# Sheet2.net
KiCad netlist of a schematic drawn in Altium Designer
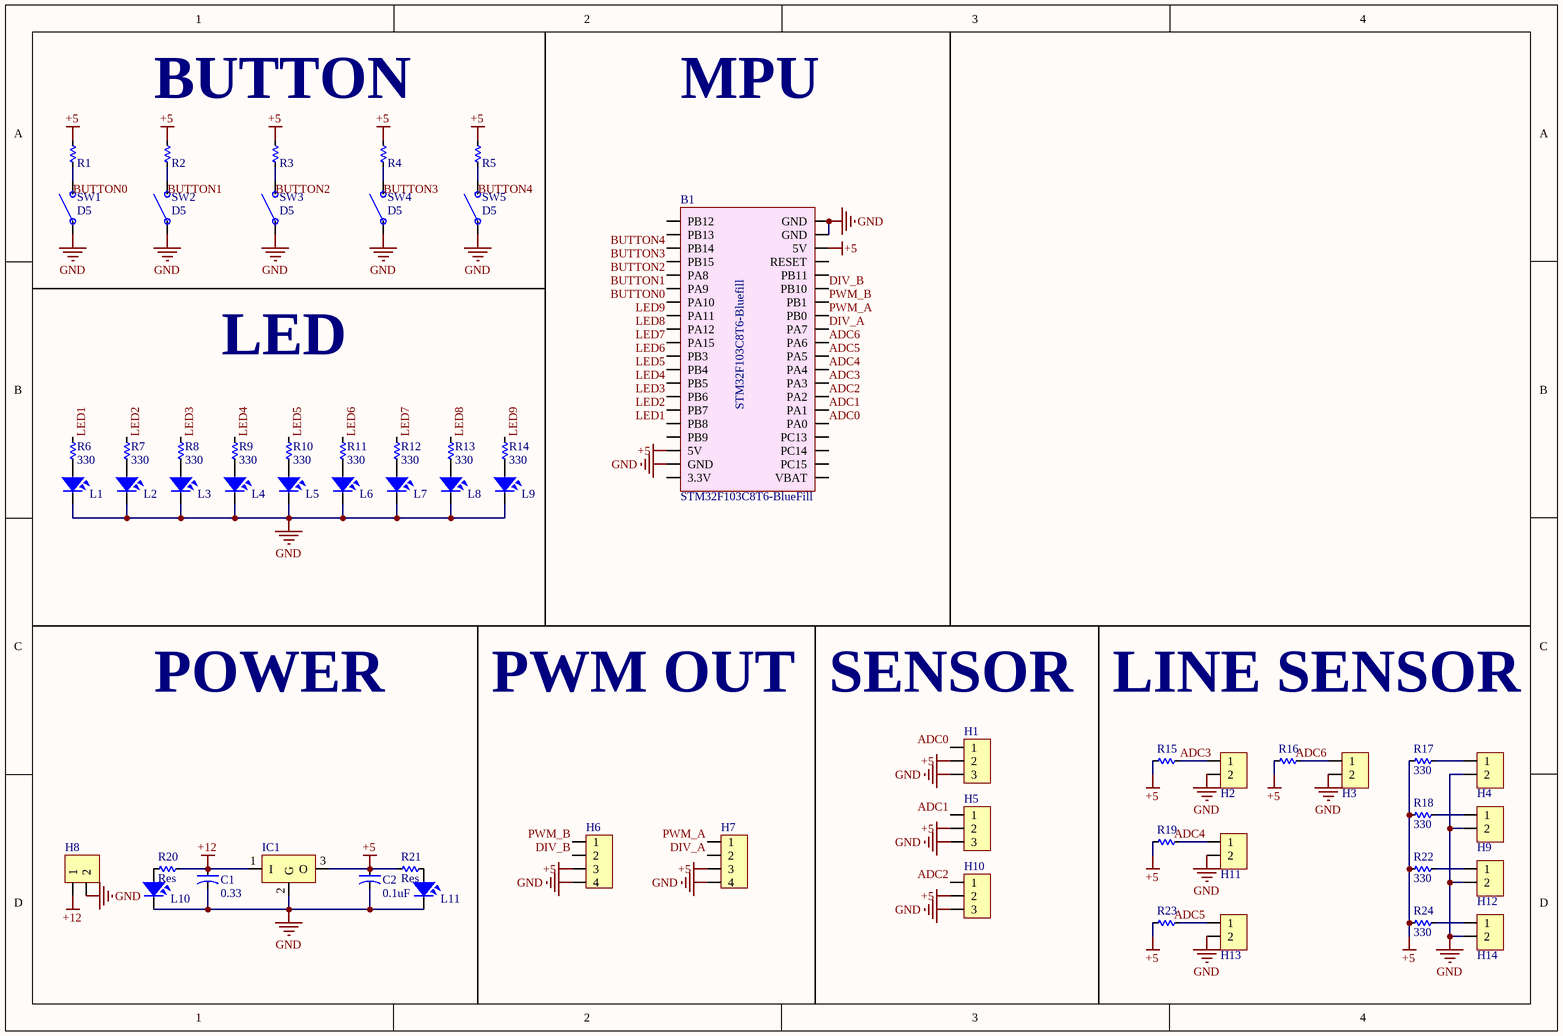
[diagram p0: Sheet2.SchDoc]

(export (version "E")
  (design (tool "Eeschema 10.0.6"))
  (components
    (comp (ref "B1")
      (value "STM32F103C8T6-BlueFill")
      (footprint "STM32F1-Bluefill")
      (libsource (lib "Schlib1") (part "STM32F103C8T6-BlueFill"))
    )
    (comp (ref "C1")
      (value "0.33")
      (footprint "CA-ALU-2.54")
      (description "Capacitor (Semiconductor SIM Model)")
      (fields (field (name "PUBLISHER") "Altium Limited"))
      (libsource (lib "LIBRARY") (part "CN-ALU-DIP"))
    )
    (comp (ref "C2")
      (value "0.1uF")
      (footprint "CA-ALU-2.54")
      (description "Capacitor (Semiconductor SIM Model)")
      (fields (field (name "PUBLISHER") "Altium Limited"))
      (libsource (lib "LIBRARY") (part "CN-ALU-DIP"))
    )
    (comp (ref "H1")
      (value "Header3")
      (footprint "Header3")
      (description "Header IDC, 3 x 1 Pin Vertical 2.54mm Pitch (Non-Boxed, Male)")
      (fields
        (field (name "MANUFACTURER") "Würth Elektronik eiSos GmbH")
        (field (name "PARTNO") "613002143121")
        (field (name "CREATED BY") "Karrer Zheng")
      )
      (libsource (lib "LIBRARY") (part "Header3"))
    )
    (comp (ref "H2")
      (value "Header2")
      (footprint "HDR2")
      (description "Header IDC, 2 x 1 Pin Vertical 2.54mm Pitch (Non-Boxed, Male)")
      (fields
        (field (name "MANUFACTURER") "Würth Elektronik eiSos GmbH")
        (field (name "PARTNO") "613002143121")
        (field (name "CREATED BY") "Karrer Zheng")
      )
      (libsource (lib "LIBRARY") (part "Header2"))
    )
    (comp (ref "H3")
      (value "Header2")
      (footprint "HDR2")
      (description "Header IDC, 2 x 1 Pin Vertical 2.54mm Pitch (Non-Boxed, Male)")
      (fields
        (field (name "MANUFACTURER") "Würth Elektronik eiSos GmbH")
        (field (name "PARTNO") "613002143121")
        (field (name "CREATED BY") "Karrer Zheng")
      )
      (libsource (lib "LIBRARY") (part "Header2"))
    )
    (comp (ref "H4")
      (value "Header2")
      (footprint "HDR2")
      (description "Header IDC, 2 x 1 Pin Vertical 2.54mm Pitch (Non-Boxed, Male)")
      (fields
        (field (name "MANUFACTURER") "Würth Elektronik eiSos GmbH")
        (field (name "PARTNO") "613002143121")
        (field (name "CREATED BY") "Karrer Zheng")
      )
      (libsource (lib "LIBRARY") (part "Header2"))
    )
    (comp (ref "H5")
      (value "Header3")
      (footprint "Header3")
      (description "Header IDC, 3 x 1 Pin Vertical 2.54mm Pitch (Non-Boxed, Male)")
      (fields
        (field (name "MANUFACTURER") "Würth Elektronik eiSos GmbH")
        (field (name "PARTNO") "613002143121")
        (field (name "CREATED BY") "Karrer Zheng")
      )
      (libsource (lib "LIBRARY") (part "Header3"))
    )
    (comp (ref "H6")
      (value "Header4")
      (footprint "Header4")
      (description "Header IDC, 4 x 1 Pin Vertical 2.54mm Pitch (Non-Boxed, Male)")
      (fields
        (field (name "MANUFACTURER") "Würth Elektronik eiSos GmbH")
        (field (name "PARTNO") "613002143121")
        (field (name "CREATED BY") "Karrer Zheng")
      )
      (libsource (lib "LIBRARY") (part "Header4"))
    )
    (comp (ref "H7")
      (value "Header4")
      (footprint "Header4")
      (description "Header IDC, 4 x 1 Pin Vertical 2.54mm Pitch (Non-Boxed, Male)")
      (fields
        (field (name "MANUFACTURER") "Würth Elektronik eiSos GmbH")
        (field (name "PARTNO") "613002143121")
        (field (name "CREATED BY") "Karrer Zheng")
      )
      (libsource (lib "LIBRARY") (part "Header4"))
    )
    (comp (ref "H8")
      (value "Header2")
      (footprint "HDR2")
      (description "Header IDC, 2 x 1 Pin Vertical 2.54mm Pitch (Non-Boxed, Male)")
      (fields
        (field (name "MANUFACTURER") "Würth Elektronik eiSos GmbH")
        (field (name "PARTNO") "613002143121")
        (field (name "CREATED BY") "Karrer Zheng")
      )
      (libsource (lib "") (part "Header2_1"))
    )
    (comp (ref "H9")
      (value "Header2")
      (footprint "HDR2")
      (description "Header IDC, 2 x 1 Pin Vertical 2.54mm Pitch (Non-Boxed, Male)")
      (fields
        (field (name "MANUFACTURER") "Würth Elektronik eiSos GmbH")
        (field (name "PARTNO") "613002143121")
        (field (name "CREATED BY") "Karrer Zheng")
      )
      (libsource (lib "LIBRARY") (part "Header2"))
    )
    (comp (ref "H10")
      (value "Header3")
      (footprint "Header3")
      (description "Header IDC, 3 x 1 Pin Vertical 2.54mm Pitch (Non-Boxed, Male)")
      (fields
        (field (name "MANUFACTURER") "Würth Elektronik eiSos GmbH")
        (field (name "PARTNO") "613002143121")
        (field (name "CREATED BY") "Karrer Zheng")
      )
      (libsource (lib "LIBRARY") (part "Header3"))
    )
    (comp (ref "H11")
      (value "Header2")
      (footprint "HDR2")
      (description "Header IDC, 2 x 1 Pin Vertical 2.54mm Pitch (Non-Boxed, Male)")
      (fields
        (field (name "MANUFACTURER") "Würth Elektronik eiSos GmbH")
        (field (name "PARTNO") "613002143121")
        (field (name "CREATED BY") "Karrer Zheng")
      )
      (libsource (lib "LIBRARY") (part "Header2"))
    )
    (comp (ref "H12")
      (value "Header2")
      (footprint "HDR2")
      (description "Header IDC, 2 x 1 Pin Vertical 2.54mm Pitch (Non-Boxed, Male)")
      (fields
        (field (name "MANUFACTURER") "Würth Elektronik eiSos GmbH")
        (field (name "PARTNO") "613002143121")
        (field (name "CREATED BY") "Karrer Zheng")
      )
      (libsource (lib "LIBRARY") (part "Header2"))
    )
    (comp (ref "H13")
      (value "Header2")
      (footprint "HDR2")
      (description "Header IDC, 2 x 1 Pin Vertical 2.54mm Pitch (Non-Boxed, Male)")
      (fields
        (field (name "MANUFACTURER") "Würth Elektronik eiSos GmbH")
        (field (name "PARTNO") "613002143121")
        (field (name "CREATED BY") "Karrer Zheng")
      )
      (libsource (lib "LIBRARY") (part "Header2"))
    )
    (comp (ref "H14")
      (value "Header2")
      (footprint "HDR2")
      (description "Header IDC, 2 x 1 Pin Vertical 2.54mm Pitch (Non-Boxed, Male)")
      (fields
        (field (name "MANUFACTURER") "Würth Elektronik eiSos GmbH")
        (field (name "PARTNO") "613002143121")
        (field (name "CREATED BY") "Karrer Zheng")
      )
      (libsource (lib "LIBRARY") (part "Header2"))
    )
    (comp (ref "IC1")
      (value "LM78xx")
      (footprint "TO220-123")
      (description "Positive Voltage Regulator")
      (fields (field (name "PUBLISHER") "Altium Limited"))
      (libsource (lib "LIBRARY") (part "LM78xx"))
    )
    (comp (ref "L1")
      (value "LED")
      (footprint "LED-3MM-YELLOW")
      (description "LED Single colour Green and Red")
      (libsource (lib "LIBRARY") (part "LED"))
    )
    (comp (ref "L2")
      (value "LED")
      (footprint "LED-3MM-YELLOW")
      (description "LED Single colour Green and Red")
      (libsource (lib "LIBRARY") (part "LED"))
    )
    (comp (ref "L3")
      (value "LED")
      (footprint "LED-3MM-YELLOW")
      (description "LED Single colour Green and Red")
      (libsource (lib "LIBRARY") (part "LED"))
    )
    (comp (ref "L4")
      (value "LED")
      (footprint "LED-3MM-YELLOW")
      (description "LED Single colour Green and Red")
      (libsource (lib "LIBRARY") (part "LED"))
    )
    (comp (ref "L5")
      (value "LED")
      (footprint "LED-3MM-YELLOW")
      (description "LED Single colour Green and Red")
      (libsource (lib "LIBRARY") (part "LED"))
    )
    (comp (ref "L6")
      (value "LED")
      (footprint "LED-3MM-YELLOW")
      (description "LED Single colour Green and Red")
      (libsource (lib "LIBRARY") (part "LED"))
    )
    (comp (ref "L7")
      (value "LED")
      (footprint "LED-3MM-YELLOW")
      (description "LED Single colour Green and Red")
      (libsource (lib "LIBRARY") (part "LED"))
    )
    (comp (ref "L8")
      (value "LED")
      (footprint "LED-3MM-YELLOW")
      (description "LED Single colour Green and Red")
      (libsource (lib "LIBRARY") (part "LED"))
    )
    (comp (ref "L9")
      (value "LED")
      (footprint "LED-3MM-YELLOW")
      (description "LED Single colour Green and Red")
      (libsource (lib "LIBRARY") (part "LED"))
    )
    (comp (ref "L10")
      (value "LED")
      (footprint "LED-3MM-YELLOW")
      (description "LED Single colour Green and Red")
      (libsource (lib "LIBRARY") (part "LED"))
    )
    (comp (ref "L11")
      (value "LED")
      (footprint "LED-3MM-YELLOW")
      (description "LED Single colour Green and Red")
      (libsource (lib "LIBRARY") (part "LED"))
    )
    (comp (ref "R1")
      (value "10K")
      (footprint "RES-1/4WD")
      (description "Res")
      (fields
        (field (name "MANUFACTURER") "Generic Components")
        (field (name "PUBLISHER") "Altium Hobart Technology Centre")
      )
      (libsource (lib "LIBRARY") (part "Res"))
    )
    (comp (ref "R2")
      (value "10K")
      (footprint "RES-1/4WD")
      (description "Res")
      (fields
        (field (name "MANUFACTURER") "Generic Components")
        (field (name "PUBLISHER") "Altium Hobart Technology Centre")
      )
      (libsource (lib "LIBRARY") (part "Res"))
    )
    (comp (ref "R3")
      (value "10K")
      (footprint "RES-1/4WD")
      (description "Res")
      (fields
        (field (name "MANUFACTURER") "Generic Components")
        (field (name "PUBLISHER") "Altium Hobart Technology Centre")
      )
      (libsource (lib "LIBRARY") (part "Res"))
    )
    (comp (ref "R4")
      (value "10K")
      (footprint "RES-1/4WD")
      (description "Res")
      (fields
        (field (name "MANUFACTURER") "Generic Components")
        (field (name "PUBLISHER") "Altium Hobart Technology Centre")
      )
      (libsource (lib "LIBRARY") (part "Res"))
    )
    (comp (ref "R5")
      (value "10K")
      (footprint "RES-1/4WD")
      (description "Res")
      (fields
        (field (name "MANUFACTURER") "Generic Components")
        (field (name "PUBLISHER") "Altium Hobart Technology Centre")
      )
      (libsource (lib "LIBRARY") (part "Res"))
    )
    (comp (ref "R6")
      (value "330")
      (footprint "RES-1/4W-SMALL")
      (description "Res")
      (fields
        (field (name "MANUFACTURER") "Generic Components")
        (field (name "PUBLISHER") "Altium Hobart Technology Centre")
      )
      (libsource (lib "LIBRARY") (part "Res"))
    )
    (comp (ref "R7")
      (value "330")
      (footprint "RES-1/4W-SMALL")
      (description "Res")
      (fields
        (field (name "MANUFACTURER") "Generic Components")
        (field (name "PUBLISHER") "Altium Hobart Technology Centre")
      )
      (libsource (lib "LIBRARY") (part "Res"))
    )
    (comp (ref "R8")
      (value "330")
      (footprint "RES-1/4W-SMALL")
      (description "Res")
      (fields
        (field (name "MANUFACTURER") "Generic Components")
        (field (name "PUBLISHER") "Altium Hobart Technology Centre")
      )
      (libsource (lib "LIBRARY") (part "Res"))
    )
    (comp (ref "R9")
      (value "330")
      (footprint "RES-1/4W-SMALL")
      (description "Res")
      (fields
        (field (name "MANUFACTURER") "Generic Components")
        (field (name "PUBLISHER") "Altium Hobart Technology Centre")
      )
      (libsource (lib "LIBRARY") (part "Res"))
    )
    (comp (ref "R10")
      (value "330")
      (footprint "RES-1/4W-SMALL")
      (description "Res")
      (fields
        (field (name "MANUFACTURER") "Generic Components")
        (field (name "PUBLISHER") "Altium Hobart Technology Centre")
      )
      (libsource (lib "LIBRARY") (part "Res"))
    )
    (comp (ref "R11")
      (value "330")
      (footprint "RES-1/4W-SMALL")
      (description "Res")
      (fields
        (field (name "MANUFACTURER") "Generic Components")
        (field (name "PUBLISHER") "Altium Hobart Technology Centre")
      )
      (libsource (lib "LIBRARY") (part "Res"))
    )
    (comp (ref "R12")
      (value "330")
      (footprint "RES-1/4W-SMALL")
      (description "Res")
      (fields
        (field (name "MANUFACTURER") "Generic Components")
        (field (name "PUBLISHER") "Altium Hobart Technology Centre")
      )
      (libsource (lib "LIBRARY") (part "Res"))
    )
    (comp (ref "R13")
      (value "330")
      (footprint "RES-1/4W-SMALL")
      (description "Res")
      (fields
        (field (name "MANUFACTURER") "Generic Components")
        (field (name "PUBLISHER") "Altium Hobart Technology Centre")
      )
      (libsource (lib "LIBRARY") (part "Res"))
    )
    (comp (ref "R14")
      (value "330")
      (footprint "RES-1/4W-SMALL")
      (description "Res")
      (fields
        (field (name "MANUFACTURER") "Generic Components")
        (field (name "PUBLISHER") "Altium Hobart Technology Centre")
      )
      (libsource (lib "LIBRARY") (part "Res"))
    )
    (comp (ref "R15")
      (value "10K")
      (footprint "RES-1/4W-SMALL")
      (description "Res")
      (fields
        (field (name "MANUFACTURER") "Generic Components")
        (field (name "PUBLISHER") "Altium Hobart Technology Centre")
      )
      (libsource (lib "LIBRARY") (part "Res"))
    )
    (comp (ref "R16")
      (value "10K")
      (footprint "RES-1/4W-SMALL")
      (description "Res")
      (fields
        (field (name "MANUFACTURER") "Generic Components")
        (field (name "PUBLISHER") "Altium Hobart Technology Centre")
      )
      (libsource (lib "LIBRARY") (part "Res"))
    )
    (comp (ref "R17")
      (value "330")
      (footprint "RES-1/4W-SMALL")
      (description "Res")
      (fields
        (field (name "MANUFACTURER") "Generic Components")
        (field (name "PUBLISHER") "Altium Hobart Technology Centre")
      )
      (libsource (lib "LIBRARY") (part "Res"))
    )
    (comp (ref "R18")
      (value "330")
      (footprint "RES-1/4W-SMALL")
      (description "Res")
      (fields
        (field (name "MANUFACTURER") "Generic Components")
        (field (name "PUBLISHER") "Altium Hobart Technology Centre")
      )
      (libsource (lib "LIBRARY") (part "Res"))
    )
    (comp (ref "R19")
      (value "10K")
      (footprint "RES-1/4W-SMALL")
      (description "Res")
      (fields
        (field (name "MANUFACTURER") "Generic Components")
        (field (name "PUBLISHER") "Altium Hobart Technology Centre")
      )
      (libsource (lib "LIBRARY") (part "Res"))
    )
    (comp (ref "R20")
      (value "Res")
      (footprint "RES-1/4W-SMALL")
      (fields
        (field (name "MANUFACTURER") "Generic Components")
        (field (name "PUBLISHER") "Altium Hobart Technology Centre")
      )
      (libsource (lib "LIBRARY") (part "Res"))
    )
    (comp (ref "R21")
      (value "Res")
      (footprint "RES-1/4W-SMALL")
      (fields
        (field (name "MANUFACTURER") "Generic Components")
        (field (name "PUBLISHER") "Altium Hobart Technology Centre")
      )
      (libsource (lib "LIBRARY") (part "Res"))
    )
    (comp (ref "R22")
      (value "330")
      (footprint "RES-1/4W-SMALL")
      (description "Res")
      (fields
        (field (name "MANUFACTURER") "Generic Components")
        (field (name "PUBLISHER") "Altium Hobart Technology Centre")
      )
      (libsource (lib "LIBRARY") (part "Res"))
    )
    (comp (ref "R23")
      (value "10K")
      (footprint "RES-1/4W-SMALL")
      (description "Res")
      (fields
        (field (name "MANUFACTURER") "Generic Components")
        (field (name "PUBLISHER") "Altium Hobart Technology Centre")
      )
      (libsource (lib "LIBRARY") (part "Res"))
    )
    (comp (ref "R24")
      (value "330")
      (footprint "RES-1/4W-SMALL")
      (description "Res")
      (fields
        (field (name "MANUFACTURER") "Generic Components")
        (field (name "PUBLISHER") "Altium Hobart Technology Centre")
      )
      (libsource (lib "LIBRARY") (part "Res"))
    )
    (comp (ref "SW1") (value "D5") (footprint "D5") (libsource (lib "Schlib1") (part "D5")))
    (comp (ref "SW2") (value "D5") (footprint "D5") (libsource (lib "Schlib1") (part "D5")))
    (comp (ref "SW3") (value "D5") (footprint "D5") (libsource (lib "Schlib1") (part "D5")))
    (comp (ref "SW4") (value "D5") (footprint "D5") (libsource (lib "Schlib1") (part "D5")))
    (comp (ref "SW5") (value "D5") (footprint "D5") (libsource (lib "Schlib1") (part "D5")))
  )
  (nets
    (net (code "1") (name "+5") (class "Default")
      (node (ref "B1") (pin "3") (pinfunction "5V_3") (pintype "passive"))
      (node (ref "B1") (pin "38") (pinfunction "5V_38") (pintype "passive"))
      (node (ref "C2") (pin "1") (pinfunction "1_1") (pintype "passive"))
      (node (ref "H1") (pin "2") (pinfunction "2_2") (pintype "passive"))
      (node (ref "H10") (pin "2") (pinfunction "2_2") (pintype "passive"))
      (node (ref "H5") (pin "2") (pinfunction "2_2") (pintype "passive"))
      (node (ref "H6") (pin "3") (pinfunction "3_3") (pintype "passive"))
      (node (ref "H7") (pin "3") (pinfunction "3_3") (pintype "passive"))
      (node (ref "IC1") (pin "3") (pinfunction "O_3") (pintype "power_in"))
      (node (ref "R1") (pin "2") (pinfunction "2_2") (pintype "passive"))
      (node (ref "R15") (pin "1") (pinfunction "1_1") (pintype "passive"))
      (node (ref "R16") (pin "1") (pinfunction "1_1") (pintype "passive"))
      (node (ref "R17") (pin "1") (pinfunction "1_1") (pintype "passive"))
      (node (ref "R18") (pin "1") (pinfunction "1_1") (pintype "passive"))
      (node (ref "R19") (pin "1") (pinfunction "1_1") (pintype "passive"))
      (node (ref "R2") (pin "2") (pinfunction "2_2") (pintype "passive"))
      (node (ref "R21") (pin "2") (pinfunction "2_2") (pintype "passive"))
      (node (ref "R22") (pin "1") (pinfunction "1_1") (pintype "passive"))
      (node (ref "R23") (pin "1") (pinfunction "1_1") (pintype "passive"))
      (node (ref "R24") (pin "1") (pinfunction "1_1") (pintype "passive"))
      (node (ref "R3") (pin "2") (pinfunction "2_2") (pintype "passive"))
      (node (ref "R4") (pin "2") (pinfunction "2_2") (pintype "passive"))
      (node (ref "R5") (pin "2") (pinfunction "2_2") (pintype "passive"))
    )
    (net (code "2") (name "+12") (class "Default")
      (node (ref "C1") (pin "1") (pinfunction "1_1") (pintype "passive"))
      (node (ref "H8") (pin "1") (pinfunction "1_1") (pintype "passive"))
      (node (ref "IC1") (pin "1") (pinfunction "I_1") (pintype "power_in"))
      (node (ref "R20") (pin "1") (pinfunction "1_1") (pintype "passive"))
    )
    (net (code "3") (name "/ADC0") (class "Default")
      (node (ref "B1") (pin "25") (pinfunction "PA0_25") (pintype "passive"))
      (node (ref "H1") (pin "1") (pinfunction "1_1") (pintype "passive"))
    )
    (net (code "4") (name "/ADC1") (class "Default")
      (node (ref "B1") (pin "26") (pinfunction "PA1_26") (pintype "passive"))
      (node (ref "H5") (pin "1") (pinfunction "1_1") (pintype "passive"))
    )
    (net (code "5") (name "/ADC2") (class "Default")
      (node (ref "B1") (pin "27") (pinfunction "PA2_27") (pintype "passive"))
      (node (ref "H10") (pin "1") (pinfunction "1_1") (pintype "passive"))
    )
    (net (code "6") (name "/ADC3") (class "Default")
      (node (ref "B1") (pin "28") (pinfunction "PA3_28") (pintype "passive"))
      (node (ref "H2") (pin "1") (pinfunction "1_1") (pintype "passive"))
      (node (ref "R15") (pin "2") (pinfunction "2_2") (pintype "passive"))
    )
    (net (code "7") (name "/ADC4") (class "Default")
      (node (ref "B1") (pin "29") (pinfunction "PA4_29") (pintype "passive"))
      (node (ref "H11") (pin "1") (pinfunction "1_1") (pintype "passive"))
      (node (ref "R19") (pin "2") (pinfunction "2_2") (pintype "passive"))
    )
    (net (code "8") (name "/ADC5") (class "Default")
      (node (ref "B1") (pin "30") (pinfunction "PA5_30") (pintype "passive"))
      (node (ref "H13") (pin "1") (pinfunction "1_1") (pintype "passive"))
      (node (ref "R23") (pin "2") (pinfunction "2_2") (pintype "passive"))
    )
    (net (code "9") (name "/ADC6") (class "Default")
      (node (ref "B1") (pin "31") (pinfunction "PA6_31") (pintype "passive"))
      (node (ref "H3") (pin "1") (pinfunction "1_1") (pintype "passive"))
      (node (ref "R16") (pin "2") (pinfunction "2_2") (pintype "passive"))
    )
    (net (code "10") (name "/BUTTON0") (class "Default")
      (node (ref "B1") (pin "14") (pinfunction "PA10_14") (pintype "passive"))
      (node (ref "R1") (pin "1") (pinfunction "1_1") (pintype "passive"))
      (node (ref "SW1") (pin "2") (pinfunction "2_2") (pintype "passive"))
    )
    (net (code "11") (name "/BUTTON1") (class "Default")
      (node (ref "B1") (pin "15") (pinfunction "PA9_15") (pintype "passive"))
      (node (ref "R2") (pin "1") (pinfunction "1_1") (pintype "passive"))
      (node (ref "SW2") (pin "2") (pinfunction "2_2") (pintype "passive"))
    )
    (net (code "12") (name "/BUTTON2") (class "Default")
      (node (ref "B1") (pin "16") (pinfunction "PA8_16") (pintype "passive"))
      (node (ref "R3") (pin "1") (pinfunction "1_1") (pintype "passive"))
      (node (ref "SW3") (pin "2") (pinfunction "2_2") (pintype "passive"))
    )
    (net (code "13") (name "/BUTTON3") (class "Default")
      (node (ref "B1") (pin "17") (pinfunction "PB15_17") (pintype "passive"))
      (node (ref "R4") (pin "1") (pinfunction "1_1") (pintype "passive"))
      (node (ref "SW4") (pin "2") (pinfunction "2_2") (pintype "passive"))
    )
    (net (code "14") (name "/BUTTON4") (class "Default")
      (node (ref "B1") (pin "18") (pinfunction "PB14_18") (pintype "passive"))
      (node (ref "R5") (pin "1") (pinfunction "1_1") (pintype "passive"))
      (node (ref "SW5") (pin "2") (pinfunction "2_2") (pintype "passive"))
    )
    (net (code "15") (name "/DIV_A") (class "Default")
      (node (ref "B1") (pin "32") (pinfunction "PA7_32") (pintype "passive"))
      (node (ref "H7") (pin "2") (pinfunction "2_2") (pintype "passive"))
    )
    (net (code "16") (name "/DIV_B") (class "Default")
      (node (ref "B1") (pin "35") (pinfunction "PB10_35") (pintype "passive"))
      (node (ref "H6") (pin "2") (pinfunction "2_2") (pintype "passive"))
    )
    (net (code "17") (name "/LED1") (class "Default")
      (node (ref "B1") (pin "5") (pinfunction "PB8_5") (pintype "passive"))
      (node (ref "R6") (pin "1") (pinfunction "1_1") (pintype "passive"))
    )
    (net (code "18") (name "/LED2") (class "Default")
      (node (ref "B1") (pin "6") (pinfunction "PB7_6") (pintype "passive"))
      (node (ref "R7") (pin "1") (pinfunction "1_1") (pintype "passive"))
    )
    (net (code "19") (name "/LED3") (class "Default")
      (node (ref "B1") (pin "7") (pinfunction "PB6_7") (pintype "passive"))
      (node (ref "R8") (pin "1") (pinfunction "1_1") (pintype "passive"))
    )
    (net (code "20") (name "/LED4") (class "Default")
      (node (ref "B1") (pin "8") (pinfunction "PB5_8") (pintype "passive"))
      (node (ref "R9") (pin "1") (pinfunction "1_1") (pintype "passive"))
    )
    (net (code "21") (name "/LED5") (class "Default")
      (node (ref "B1") (pin "9") (pinfunction "PB4_9") (pintype "passive"))
      (node (ref "R10") (pin "1") (pinfunction "1_1") (pintype "passive"))
    )
    (net (code "22") (name "/LED6") (class "Default")
      (node (ref "B1") (pin "10") (pinfunction "PB3_10") (pintype "passive"))
      (node (ref "R11") (pin "1") (pinfunction "1_1") (pintype "passive"))
    )
    (net (code "23") (name "/LED7") (class "Default")
      (node (ref "B1") (pin "11") (pinfunction "PA15_11") (pintype "passive"))
      (node (ref "R12") (pin "1") (pinfunction "1_1") (pintype "passive"))
    )
    (net (code "24") (name "/LED8") (class "Default")
      (node (ref "B1") (pin "12") (pinfunction "PA12_12") (pintype "passive"))
      (node (ref "R13") (pin "1") (pinfunction "1_1") (pintype "passive"))
    )
    (net (code "25") (name "/LED9") (class "Default")
      (node (ref "B1") (pin "13") (pinfunction "PA11_13") (pintype "passive"))
      (node (ref "R14") (pin "1") (pinfunction "1_1") (pintype "passive"))
    )
    (net (code "26") (name "/PWM_A") (class "Default")
      (node (ref "B1") (pin "33") (pinfunction "PB0_33") (pintype "passive"))
      (node (ref "H7") (pin "1") (pinfunction "1_1") (pintype "passive"))
    )
    (net (code "27") (name "/PWM_B") (class "Default")
      (node (ref "B1") (pin "34") (pinfunction "PB1_34") (pintype "passive"))
      (node (ref "H6") (pin "1") (pinfunction "1_1") (pintype "passive"))
    )
    (net (code "28") (name "GND") (class "Default")
      (node (ref "B1") (pin "2") (pinfunction "GND_2") (pintype "passive"))
      (node (ref "B1") (pin "39") (pinfunction "GND_39") (pintype "passive"))
      (node (ref "B1") (pin "40") (pinfunction "GND_40") (pintype "passive"))
      (node (ref "C1") (pin "2") (pinfunction "2_2") (pintype "passive"))
      (node (ref "C2") (pin "2") (pinfunction "2_2") (pintype "passive"))
      (node (ref "H1") (pin "3") (pinfunction "3_3") (pintype "passive"))
      (node (ref "H10") (pin "3") (pinfunction "3_3") (pintype "passive"))
      (node (ref "H11") (pin "2") (pinfunction "2_2") (pintype "passive"))
      (node (ref "H12") (pin "2") (pinfunction "2_2") (pintype "passive"))
      (node (ref "H13") (pin "2") (pinfunction "2_2") (pintype "passive"))
      (node (ref "H14") (pin "2") (pinfunction "2_2") (pintype "passive"))
      (node (ref "H2") (pin "2") (pinfunction "2_2") (pintype "passive"))
      (node (ref "H3") (pin "2") (pinfunction "2_2") (pintype "passive"))
      (node (ref "H4") (pin "2") (pinfunction "2_2") (pintype "passive"))
      (node (ref "H5") (pin "3") (pinfunction "3_3") (pintype "passive"))
      (node (ref "H6") (pin "4") (pinfunction "4_4") (pintype "passive"))
      (node (ref "H7") (pin "4") (pinfunction "4_4") (pintype "passive"))
      (node (ref "H8") (pin "2") (pinfunction "2_2") (pintype "passive"))
      (node (ref "H9") (pin "2") (pinfunction "2_2") (pintype "passive"))
      (node (ref "IC1") (pin "2") (pinfunction "G_2") (pintype "power_in"))
      (node (ref "L1") (pin "2") (pinfunction "2_2") (pintype "passive"))
      (node (ref "L10") (pin "2") (pinfunction "2_2") (pintype "passive"))
      (node (ref "L11") (pin "2") (pinfunction "2_2") (pintype "passive"))
      (node (ref "L2") (pin "2") (pinfunction "2_2") (pintype "passive"))
      (node (ref "L3") (pin "2") (pinfunction "2_2") (pintype "passive"))
      (node (ref "L4") (pin "2") (pinfunction "2_2") (pintype "passive"))
      (node (ref "L5") (pin "2") (pinfunction "2_2") (pintype "passive"))
      (node (ref "L6") (pin "2") (pinfunction "2_2") (pintype "passive"))
      (node (ref "L7") (pin "2") (pinfunction "2_2") (pintype "passive"))
      (node (ref "L8") (pin "2") (pinfunction "2_2") (pintype "passive"))
      (node (ref "L9") (pin "2") (pinfunction "2_2") (pintype "passive"))
      (node (ref "SW1") (pin "1") (pinfunction "1_1") (pintype "passive"))
      (node (ref "SW2") (pin "1") (pinfunction "1_1") (pintype "passive"))
      (node (ref "SW3") (pin "1") (pinfunction "1_1") (pintype "passive"))
      (node (ref "SW4") (pin "1") (pinfunction "1_1") (pintype "passive"))
      (node (ref "SW5") (pin "1") (pinfunction "1_1") (pintype "passive"))
    )
    (net (code "29") (name "Net-(H4-Pad1)") (class "Default")
      (node (ref "H4") (pin "1") (pinfunction "1_1") (pintype "passive"))
      (node (ref "R17") (pin "2") (pinfunction "2_2") (pintype "passive"))
    )
    (net (code "30") (name "Net-(H9-Pad1)") (class "Default")
      (node (ref "H9") (pin "1") (pinfunction "1_1") (pintype "passive"))
      (node (ref "R18") (pin "2") (pinfunction "2_2") (pintype "passive"))
    )
    (net (code "31") (name "Net-(H12-Pad1)") (class "Default")
      (node (ref "H12") (pin "1") (pinfunction "1_1") (pintype "passive"))
      (node (ref "R22") (pin "2") (pinfunction "2_2") (pintype "passive"))
    )
    (net (code "32") (name "Net-(H14-Pad1)") (class "Default")
      (node (ref "H14") (pin "1") (pinfunction "1_1") (pintype "passive"))
      (node (ref "R24") (pin "2") (pinfunction "2_2") (pintype "passive"))
    )
    (net (code "33") (name "Net-(L1-Pad1)") (class "Default")
      (node (ref "L1") (pin "1") (pinfunction "1_1") (pintype "passive"))
      (node (ref "R6") (pin "2") (pinfunction "2_2") (pintype "passive"))
    )
    (net (code "34") (name "Net-(L2-Pad1)") (class "Default")
      (node (ref "L2") (pin "1") (pinfunction "1_1") (pintype "passive"))
      (node (ref "R7") (pin "2") (pinfunction "2_2") (pintype "passive"))
    )
    (net (code "35") (name "Net-(L3-Pad1)") (class "Default")
      (node (ref "L3") (pin "1") (pinfunction "1_1") (pintype "passive"))
      (node (ref "R8") (pin "2") (pinfunction "2_2") (pintype "passive"))
    )
    (net (code "36") (name "Net-(L4-Pad1)") (class "Default")
      (node (ref "L4") (pin "1") (pinfunction "1_1") (pintype "passive"))
      (node (ref "R9") (pin "2") (pinfunction "2_2") (pintype "passive"))
    )
    (net (code "37") (name "Net-(L5-Pad1)") (class "Default")
      (node (ref "L5") (pin "1") (pinfunction "1_1") (pintype "passive"))
      (node (ref "R10") (pin "2") (pinfunction "2_2") (pintype "passive"))
    )
    (net (code "38") (name "Net-(L6-Pad1)") (class "Default")
      (node (ref "L6") (pin "1") (pinfunction "1_1") (pintype "passive"))
      (node (ref "R11") (pin "2") (pinfunction "2_2") (pintype "passive"))
    )
    (net (code "39") (name "Net-(L7-Pad1)") (class "Default")
      (node (ref "L7") (pin "1") (pinfunction "1_1") (pintype "passive"))
      (node (ref "R12") (pin "2") (pinfunction "2_2") (pintype "passive"))
    )
    (net (code "40") (name "Net-(L8-Pad1)") (class "Default")
      (node (ref "L8") (pin "1") (pinfunction "1_1") (pintype "passive"))
      (node (ref "R13") (pin "2") (pinfunction "2_2") (pintype "passive"))
    )
    (net (code "41") (name "Net-(L9-Pad1)") (class "Default")
      (node (ref "L9") (pin "1") (pinfunction "1_1") (pintype "passive"))
      (node (ref "R14") (pin "2") (pinfunction "2_2") (pintype "passive"))
    )
    (net (code "42") (name "Net-(L10-Pad1)") (class "Default")
      (node (ref "L10") (pin "1") (pinfunction "1_1") (pintype "passive"))
      (node (ref "R20") (pin "2") (pinfunction "2_2") (pintype "passive"))
    )
    (net (code "43") (name "Net-(L11-Pad1)") (class "Default")
      (node (ref "L11") (pin "1") (pinfunction "1_1") (pintype "passive"))
      (node (ref "R21") (pin "1") (pinfunction "1_1") (pintype "passive"))
    )
    (net (code "44") (name "unconnected-(B1-3.3V-Pad1)") (class "Default")
      (node (ref "B1") (pin "1") (pinfunction "3.3V_1") (pintype "passive"))
    )
    (net (code "45") (name "unconnected-(B1-PB9-Pad4)") (class "Default")
      (node (ref "B1") (pin "4") (pinfunction "PB9_4") (pintype "passive"))
    )
    (net (code "46") (name "unconnected-(B1-PB11-Pad36)") (class "Default")
      (node (ref "B1") (pin "36") (pinfunction "PB11_36") (pintype "passive"))
    )
    (net (code "47") (name "unconnected-(B1-PB12-Pad20)") (class "Default")
      (node (ref "B1") (pin "20") (pinfunction "PB12_20") (pintype "passive"))
    )
    (net (code "48") (name "unconnected-(B1-PB13-Pad19)") (class "Default")
      (node (ref "B1") (pin "19") (pinfunction "PB13_19") (pintype "passive"))
    )
    (net (code "49") (name "unconnected-(B1-PC13-Pad24)") (class "Default")
      (node (ref "B1") (pin "24") (pinfunction "PC13_24") (pintype "passive"))
    )
    (net (code "50") (name "unconnected-(B1-PC14-Pad23)") (class "Default")
      (node (ref "B1") (pin "23") (pinfunction "PC14_23") (pintype "passive"))
    )
    (net (code "51") (name "unconnected-(B1-PC15-Pad22)") (class "Default")
      (node (ref "B1") (pin "22") (pinfunction "PC15_22") (pintype "passive"))
    )
    (net (code "52") (name "unconnected-(B1-RESET-Pad37)") (class "Default")
      (node (ref "B1") (pin "37") (pinfunction "RESET_37") (pintype "passive"))
    )
    (net (code "53") (name "unconnected-(B1-VBAT-Pad21)") (class "Default")
      (node (ref "B1") (pin "21") (pinfunction "VBAT_21") (pintype "passive"))
    )
  )
)
